# uvnitr-stanice.net
KiCad netlist of a schematic drawn in EAGLE
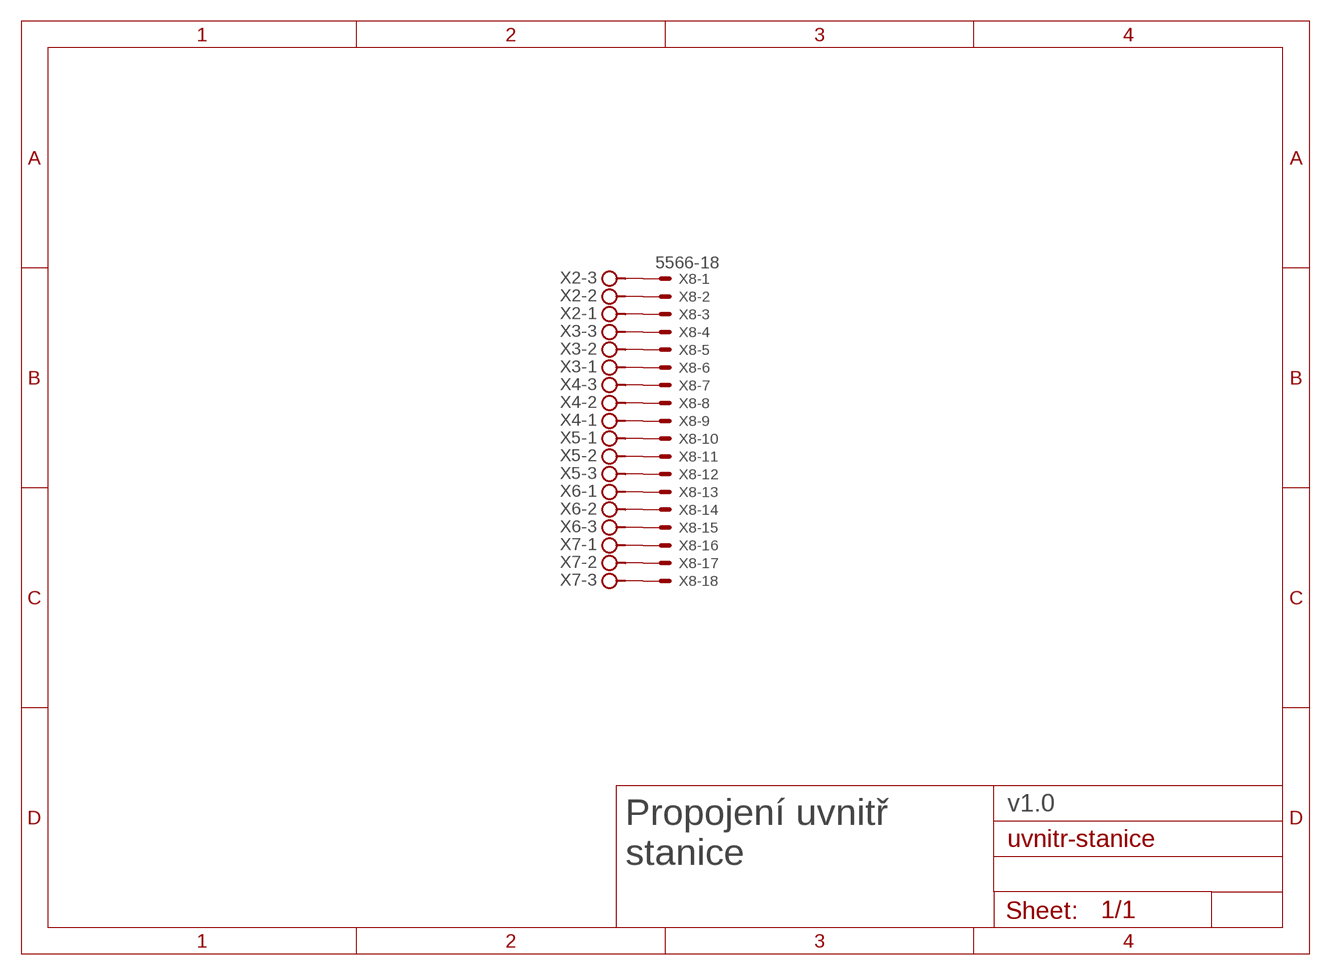
[diagram p0: schematic, sheet 1]

(export (version "E")
  (design (tool "Eeschema 10.0.6"))
  (components
    (comp (ref "X2")
      (value "ARK500/3")
      (footprint "eagle-import:ARK500_3")
      (libsource (lib "eagle-import") (part "ARK500/3"))
    )
    (comp (ref "X3")
      (value "ARK500/3")
      (footprint "eagle-import:ARK500_3")
      (libsource (lib "eagle-import") (part "ARK500/3"))
    )
    (comp (ref "X4")
      (value "ARK500/3")
      (footprint "eagle-import:ARK500_3")
      (libsource (lib "eagle-import") (part "ARK500/3"))
    )
    (comp (ref "X5")
      (value "ARK500/3")
      (footprint "eagle-import:ARK500_3")
      (libsource (lib "eagle-import") (part "ARK500/3"))
    )
    (comp (ref "X6")
      (value "ARK500/3")
      (footprint "eagle-import:ARK500_3")
      (libsource (lib "eagle-import") (part "ARK500/3"))
    )
    (comp (ref "X7")
      (value "ARK500/3")
      (footprint "eagle-import:ARK500_3")
      (libsource (lib "eagle-import") (part "ARK500/3"))
    )
    (comp (ref "X8")
      (value "5566-18")
      (footprint "eagle-import:5566-18")
      (fields (field (name "MF") "MOLEX"))
      (libsource (lib "eagle-import") (part "5566-18"))
    )
  )
  (nets
    (net (code "1") (name "Net-(X2B-1)") (class "Default")
      (node (ref "X2") (pin "2") (pinfunction "1_2") (pintype "passive"))
      (node (ref "X8") (pin "2") (pinfunction "S_2") (pintype "passive"))
    )
    (net (code "2") (name "Net-(X2C-1)") (class "Default")
      (node (ref "X2") (pin "3") (pinfunction "1_3") (pintype "passive"))
      (node (ref "X8") (pin "1") (pinfunction "S_1") (pintype "passive"))
    )
    (net (code "3") (name "Net-(X3B-1)") (class "Default")
      (node (ref "X3") (pin "2") (pinfunction "1_2") (pintype "passive"))
      (node (ref "X8") (pin "5") (pinfunction "S_5") (pintype "passive"))
    )
    (net (code "4") (name "Net-(X3C-1)") (class "Default")
      (node (ref "X3") (pin "3") (pinfunction "1_3") (pintype "passive"))
      (node (ref "X8") (pin "4") (pinfunction "S_4") (pintype "passive"))
    )
    (net (code "5") (name "Net-(X4B-1)") (class "Default")
      (node (ref "X4") (pin "2") (pinfunction "1_2") (pintype "passive"))
      (node (ref "X8") (pin "8") (pinfunction "S_8") (pintype "passive"))
    )
    (net (code "6") (name "Net-(X4C-1)") (class "Default")
      (node (ref "X4") (pin "3") (pinfunction "1_3") (pintype "passive"))
      (node (ref "X8") (pin "7") (pinfunction "S_7") (pintype "passive"))
    )
    (net (code "7") (name "Net-(X5B-1)") (class "Default")
      (node (ref "X5") (pin "2") (pinfunction "1_2") (pintype "passive"))
      (node (ref "X8") (pin "11") (pinfunction "S_11") (pintype "passive"))
    )
    (net (code "8") (name "Net-(X5C-1)") (class "Default")
      (node (ref "X5") (pin "3") (pinfunction "1_3") (pintype "passive"))
      (node (ref "X8") (pin "12") (pinfunction "S_12") (pintype "passive"))
    )
    (net (code "9") (name "Net-(X6B-1)") (class "Default")
      (node (ref "X6") (pin "2") (pinfunction "1_2") (pintype "passive"))
      (node (ref "X8") (pin "14") (pinfunction "S_14") (pintype "passive"))
    )
    (net (code "10") (name "Net-(X6C-1)") (class "Default")
      (node (ref "X6") (pin "3") (pinfunction "1_3") (pintype "passive"))
      (node (ref "X8") (pin "15") (pinfunction "S_15") (pintype "passive"))
    )
    (net (code "11") (name "Net-(X7B-1)") (class "Default")
      (node (ref "X7") (pin "2") (pinfunction "1_2") (pintype "passive"))
      (node (ref "X8") (pin "17") (pinfunction "S_17") (pintype "passive"))
    )
    (net (code "12") (name "Net-(X7C-1)") (class "Default")
      (node (ref "X7") (pin "3") (pinfunction "1_3") (pintype "passive"))
      (node (ref "X8") (pin "18") (pinfunction "S_18") (pintype "passive"))
    )
    (net (code "13") (name "Net-(X8B-S)") (class "Default")
      (node (ref "X5") (pin "1") (pinfunction "1_1") (pintype "passive"))
      (node (ref "X8") (pin "10") (pinfunction "S_10") (pintype "passive"))
    )
    (net (code "14") (name "Net-(X8E-S)") (class "Default")
      (node (ref "X6") (pin "1") (pinfunction "1_1") (pintype "passive"))
      (node (ref "X8") (pin "13") (pinfunction "S_13") (pintype "passive"))
    )
    (net (code "15") (name "Net-(X8H-S)") (class "Default")
      (node (ref "X7") (pin "1") (pinfunction "1_1") (pintype "passive"))
      (node (ref "X8") (pin "16") (pinfunction "S_16") (pintype "passive"))
    )
    (net (code "16") (name "Net-(X8L-S)") (class "Default")
      (node (ref "X2") (pin "1") (pinfunction "1_1") (pintype "passive"))
      (node (ref "X8") (pin "3") (pinfunction "S_3") (pintype "passive"))
    )
    (net (code "17") (name "Net-(X8O-S)") (class "Default")
      (node (ref "X3") (pin "1") (pinfunction "1_1") (pintype "passive"))
      (node (ref "X8") (pin "6") (pinfunction "S_6") (pintype "passive"))
    )
    (net (code "18") (name "Net-(X8R-S)") (class "Default")
      (node (ref "X4") (pin "1") (pinfunction "1_1") (pintype "passive"))
      (node (ref "X8") (pin "9") (pinfunction "S_9") (pintype "passive"))
    )
  )
)
